# X-mas-star_V2.net
KiCad netlist of a schematic drawn in EAGLE
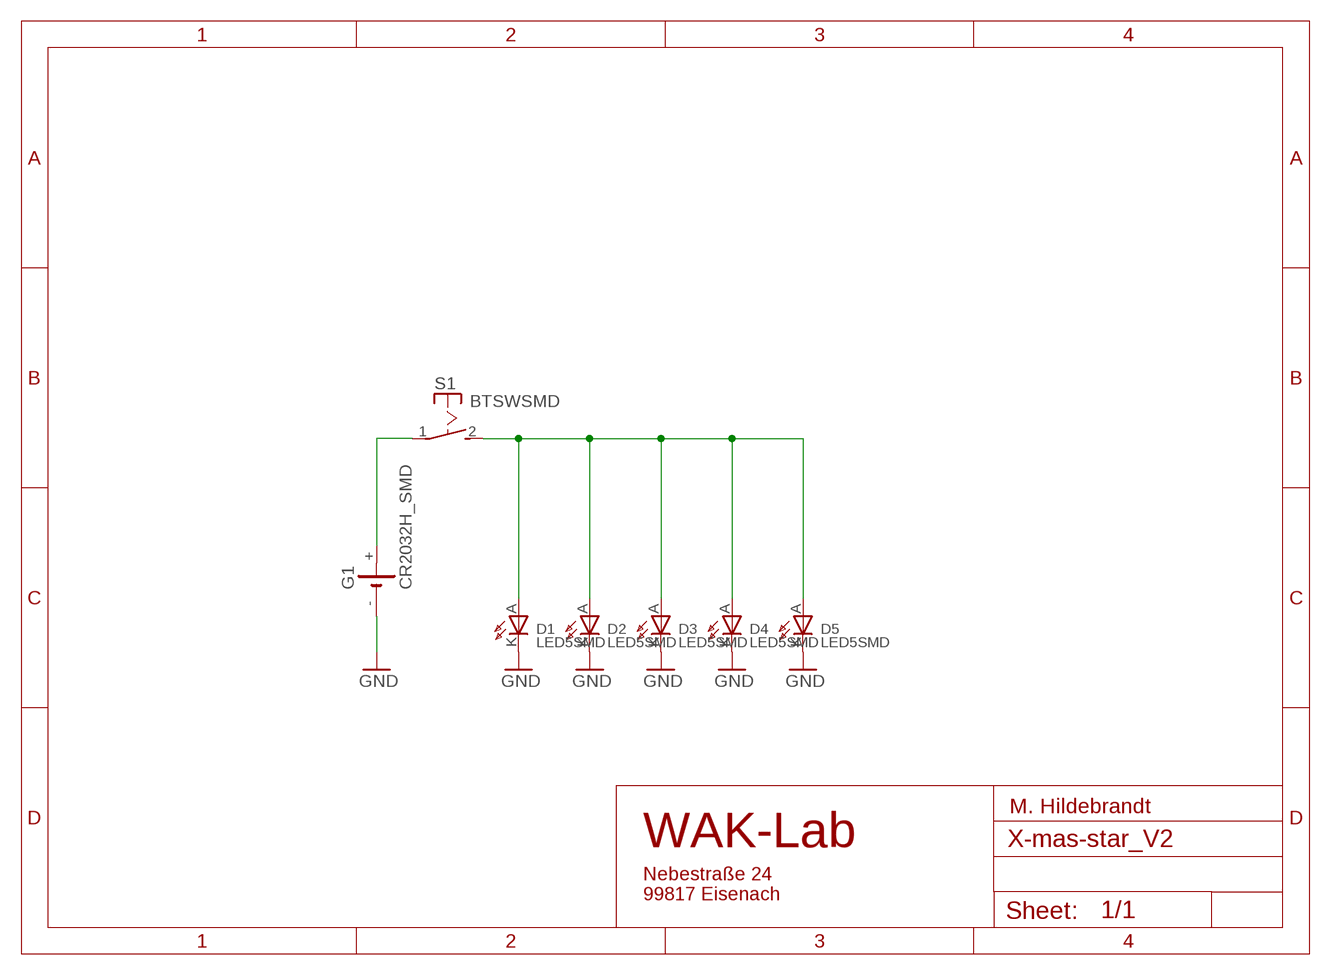
[diagram p0: schematic, sheet 1]

(export (version "E")
  (design (tool "Eeschema 10.0.6"))
  (components
    (comp (ref "D1")
      (value "LED5SMD")
      (footprint "eagle-import:LED5MM_PADS")
      (libsource (lib "eagle-import") (part "LED5SMD"))
    )
    (comp (ref "D2")
      (value "LED5SMD")
      (footprint "eagle-import:LED5MM_PADS")
      (libsource (lib "eagle-import") (part "LED5SMD"))
    )
    (comp (ref "D3")
      (value "LED5SMD")
      (footprint "eagle-import:LED5MM_PADS")
      (libsource (lib "eagle-import") (part "LED5SMD"))
    )
    (comp (ref "D4")
      (value "LED5SMD")
      (footprint "eagle-import:LED5MM_PADS")
      (libsource (lib "eagle-import") (part "LED5SMD"))
    )
    (comp (ref "D5")
      (value "LED5SMD")
      (footprint "eagle-import:LED5MM_PADS")
      (libsource (lib "eagle-import") (part "LED5SMD"))
    )
    (comp (ref "G1")
      (value "CR2032H_SMD")
      (footprint "eagle-import:CR2032H_SMD")
      (libsource (lib "eagle-import") (part "CR2032H_SMD"))
    )
    (comp (ref "S1")
      (value "BTSWSMD")
      (footprint "eagle-import:BTSW_SMD")
      (libsource (lib "eagle-import") (part "BTSWSMD"))
    )
  )
  (nets
    (net (code "1") (name "GND") (class "Default")
      (node (ref "D1") (pin "K") (pinfunction "K_K") (pintype "passive"))
      (node (ref "D2") (pin "K") (pinfunction "K_K") (pintype "passive"))
      (node (ref "D3") (pin "K") (pinfunction "K_K") (pintype "passive"))
      (node (ref "D4") (pin "K") (pinfunction "K_K") (pintype "passive"))
      (node (ref "D5") (pin "K") (pinfunction "K_K") (pintype "passive"))
      (node (ref "G1") (pin "-") (pinfunction "-_-") (pintype "passive"))
    )
    (net (code "2") (name "Net-(S1-P)") (class "Default")
      (node (ref "G1") (pin "+") (pinfunction "+_+") (pintype "passive"))
      (node (ref "S1") (pin "1") (pinfunction "P_1") (pintype "passive"))
    )
    (net (code "3") (name "Net-(S1-S)") (class "Default")
      (node (ref "D1") (pin "A") (pinfunction "A_A") (pintype "passive"))
      (node (ref "D2") (pin "A") (pinfunction "A_A") (pintype "passive"))
      (node (ref "D3") (pin "A") (pinfunction "A_A") (pintype "passive"))
      (node (ref "D4") (pin "A") (pinfunction "A_A") (pintype "passive"))
      (node (ref "D5") (pin "A") (pinfunction "A_A") (pintype "passive"))
      (node (ref "S1") (pin "2") (pinfunction "S_2") (pintype "passive"))
    )
  )
)
